# AnalogInterface.net
KiCad netlist of a schematic drawn in Altium Designer
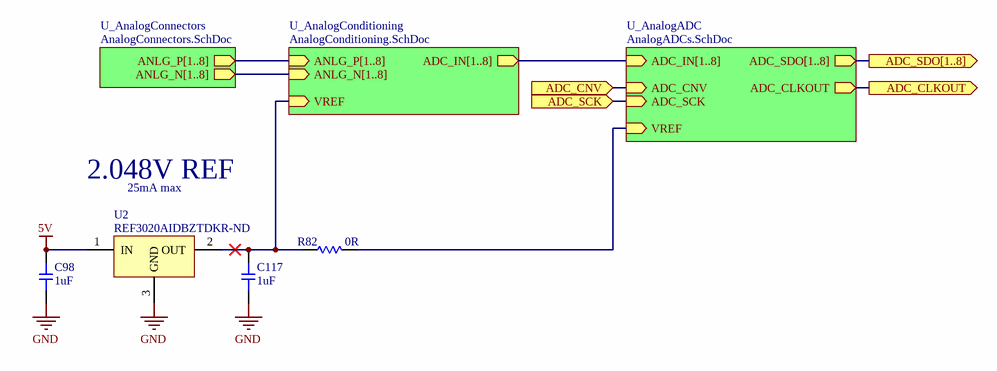
[diagram p0: AnalogInterface.SchDoc]

(export (version "E")
  (design (tool "Eeschema 10.0.6"))
  (components
    (comp (ref "C98")
      (value "1uF")
      (footprint "0603-CAP")
      (description "Capacitor")
      (libsource (lib "AMDC") (part "Capacitor"))
    )
    (comp (ref "C117")
      (value "1uF")
      (footprint "0603-CAP")
      (description "Capacitor")
      (libsource (lib "AMDC") (part "Capacitor"))
    )
    (comp (ref "R82")
      (value "0R")
      (footprint "1206-RES")
      (description "Resistor")
      (libsource (lib "AMDC") (part "Resistor"))
    )
    (comp (ref "U2")
      (value "REF3020AIDBZT")
      (footprint "SOT23-3")
      (description "Series Voltage Reference IC ±0.2% 25mA SOT-23-3")
      (fields (field (name "SUPPLIER PART NUMBER 1") "REF3020AIDBZTDKR-ND"))
      (libsource (lib "AMDC") (part "REF3020AIDBZT"))
    )
  )
  (nets
    (net (code "16") (name "/VREF") (class "Default")
      (node (ref "R82") (pin "2") (pinfunction "2_2") (pintype "passive"))
    )
    (net (code "17") (name "/VREF_1") (class "Default")
      (node (ref "C117") (pin "2") (pinfunction "2_2") (pintype "passive"))
      (node (ref "R82") (pin "1") (pinfunction "1_1") (pintype "passive"))
      (node (ref "U2") (pin "2") (pinfunction "OUT_2") (pintype "passive"))
    )
    (net (code "18") (name "5V") (class "Default")
      (node (ref "C98") (pin "2") (pinfunction "2_2") (pintype "passive"))
      (node (ref "U2") (pin "1") (pinfunction "IN_1") (pintype "passive"))
    )
    (net (code "19") (name "GND") (class "Default")
      (node (ref "C117") (pin "1") (pinfunction "1_1") (pintype "passive"))
      (node (ref "C98") (pin "1") (pinfunction "1_1") (pintype "passive"))
      (node (ref "U2") (pin "3") (pinfunction "GND_3") (pintype "passive"))
    )
  )
)
